# Zoom_Camrea_Controller_V3_0.net
KiCad netlist of a schematic drawn in Altium Designer
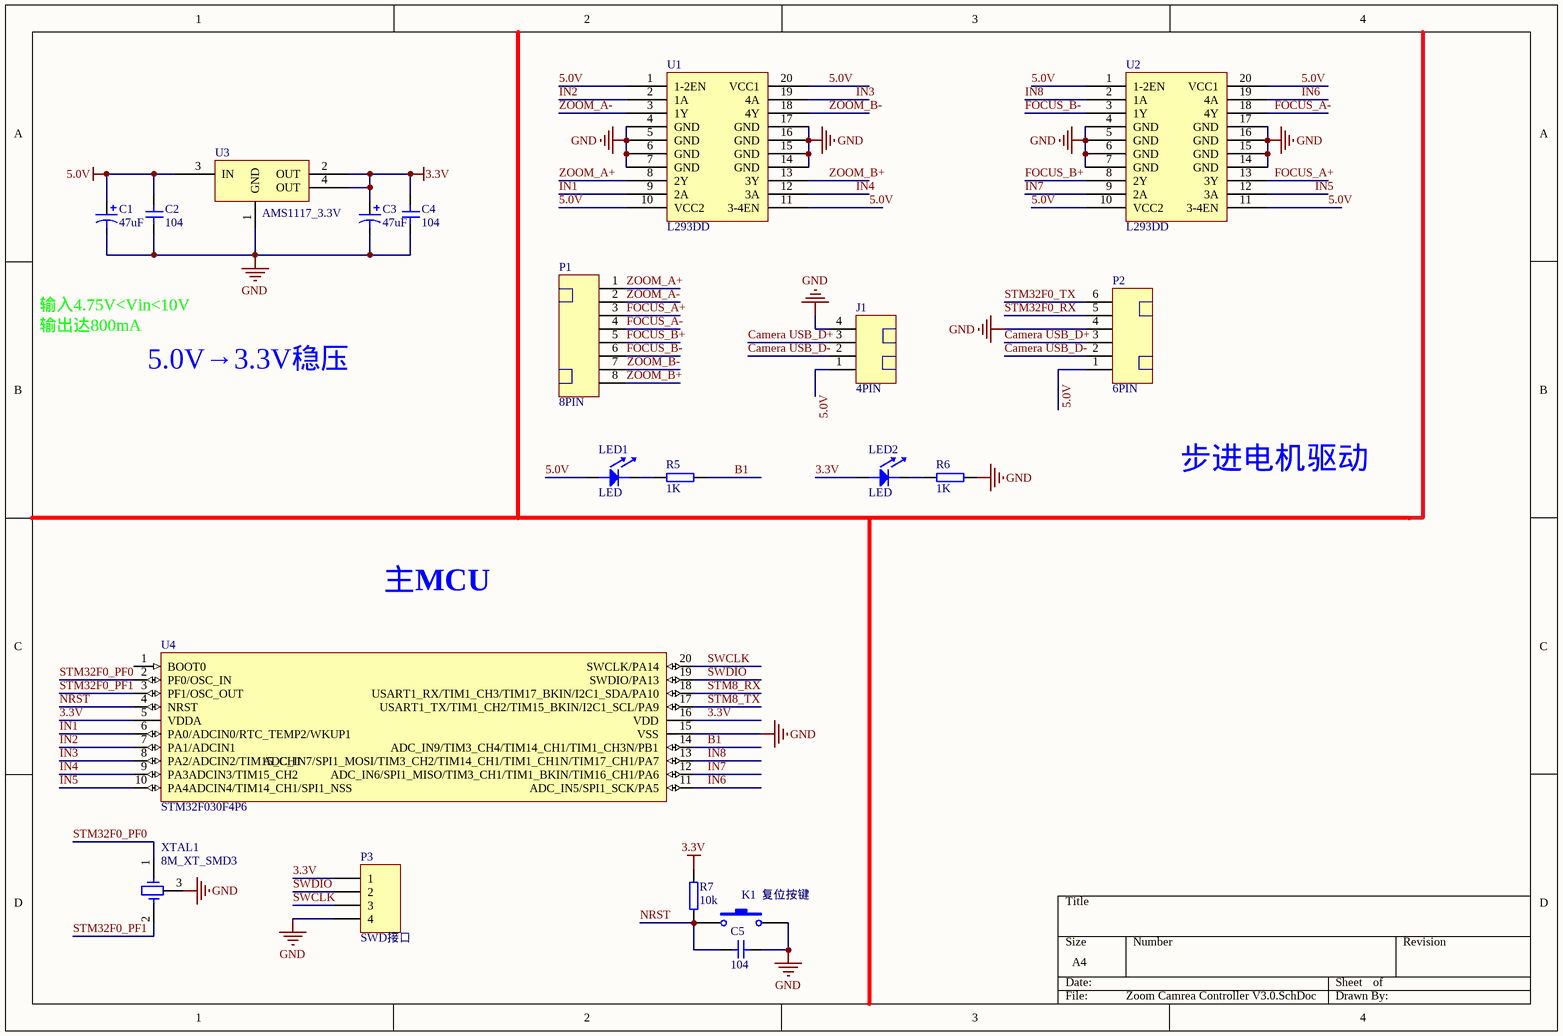
[diagram p0: Zoom Camrea Controller V3.0.SchDoc]

(export (version "E")
  (design (tool "Eeschema 10.0.6"))
  (components
    (comp (ref "C1")
      (value "47uF")
      (footprint "TAJ-A")
      (description "极性贴片电容")
      (libsource (lib "集大电协1.1.0") (part "Pol Cap"))
    )
    (comp (ref "C2")
      (value "104")
      (footprint "0805C")
      (description "无极贴片电容")
      (libsource (lib "集大电协1.1.0") (part "Cap1"))
    )
    (comp (ref "C3")
      (value "47uF")
      (footprint "TAJ-A")
      (description "极性贴片电容")
      (libsource (lib "集大电协1.1.0") (part "Pol Cap"))
    )
    (comp (ref "C4")
      (value "104")
      (footprint "0805C")
      (description "无极贴片电容")
      (libsource (lib "集大电协1.1.0") (part "Cap1"))
    )
    (comp (ref "C5")
      (value "104")
      (footprint "0805C")
      (description "无极贴片电容")
      (libsource (lib "集大电协1.1.0") (part "Cap1"))
    )
    (comp (ref "J1") (value "4PIN") (footprint "MX1.25WS-4P") (libsource (lib "MX") (part "MX1.25-4P")))
    (comp (ref "K1")
      (value "复位按键")
      (footprint "贴片按键")
      (description "轻触开关")
      (libsource (lib "集大电协1.1.0") (part "贴片按键"))
    )
    (comp (ref "LED1")
      (value "LED")
      (footprint "0805LED(RED)")
      (description "发光二极管")
      (libsource (lib "集大电协1.5") (part "LED"))
    )
    (comp (ref "LED2")
      (value "LED")
      (footprint "0805LED(RED)")
      (description "发光二极管")
      (libsource (lib "集大电协1.5") (part "LED"))
    )
    (comp (ref "P1") (value "8PIN") (footprint "MX1.25WS-8P") (libsource (lib "MX") (part "MX1.25-8P")))
    (comp (ref "P2") (value "6PIN") (footprint "MX1.25WS-6P") (libsource (lib "MX") (part "MX1.25-6P")))
    (comp (ref "P3")
      (value "SWD接口")
      (footprint "Header 4")
      (description "Header, 4-Pin")
      (fields (field (name "PUBLISHER") "Altium Limited"))
      (libsource (lib "Miscellaneous Connectors") (part "Header 4"))
    )
    (comp (ref "R5")
      (value "1K")
      (footprint "0805R")
      (description "电阻")
      (libsource (lib "集大电协1.1.2") (part "Res"))
    )
    (comp (ref "R6")
      (value "1K")
      (footprint "0805R")
      (description "电阻")
      (libsource (lib "集大电协1.1.2") (part "Res"))
    )
    (comp (ref "R7")
      (value "10k")
      (footprint "0805R")
      (description "电阻")
      (libsource (lib "集大电协1.1.0") (part "Res"))
    )
    (comp (ref "U1") (value "L293DD") (footprint "SOP-20") (libsource (lib "集大电协1.1.2") (part "L293D")))
    (comp (ref "U2") (value "L293DD") (footprint "SOP-20") (libsource (lib "集大电协1.1.2") (part "L293D")))
    (comp (ref "U3")
      (value "AMS1117_3.3V")
      (footprint "SOT-223")
      (description "电源芯片")
      (libsource (lib "集大电协1.1.0") (part "AMS1117-3.3V/5.0V"))
    )
    (comp (ref "U4")
      (value "STM32F030F4P6")
      (footprint "STM32F030")
      (libsource (lib "STM32系列单片机") (part "STM32F030F4P6"))
    )
    (comp (ref "XTAL1")
      (value "8M_XT_SMD3")
      (footprint "三脚贴片8M晶振")
      (libsource (lib "集大电协1.1.0") (part "XTAL三脚贴片晶振"))
    )
  )
  (nets
    (net (code "1") (name "/B1") (class "Default")
      (node (ref "R5") (pin "2") (pinfunction "2_2") (pintype "passive"))
      (node (ref "U4") (pin "14") (pinfunction "ADC_IN9/TIM3_CH4/TIM14_CH1/TIM1_CH3N/PB1_14") (pintype "bidirectional"))
    )
    (net (code "2") (name "/Camera USB_D+") (class "Default")
      (node (ref "J1") (pin "3") (pinfunction "3_3") (pintype "passive"))
      (node (ref "P2") (pin "3") (pinfunction "3_3") (pintype "passive"))
    )
    (net (code "3") (name "/Camera USB_D-") (class "Default")
      (node (ref "J1") (pin "2") (pinfunction "2_2") (pintype "passive"))
      (node (ref "P2") (pin "2") (pinfunction "2_2") (pintype "passive"))
    )
    (net (code "4") (name "/FOCUS_A+") (class "Default")
      (node (ref "P1") (pin "3") (pinfunction "3_3") (pintype "passive"))
      (node (ref "U2") (pin "13") (pinfunction "3Y_13") (pintype "passive"))
    )
    (net (code "5") (name "/FOCUS_A-") (class "Default")
      (node (ref "P1") (pin "4") (pinfunction "4_4") (pintype "passive"))
      (node (ref "U2") (pin "18") (pinfunction "4Y_18") (pintype "passive"))
    )
    (net (code "6") (name "/FOCUS_B+") (class "Default")
      (node (ref "P1") (pin "5") (pinfunction "5_5") (pintype "passive"))
      (node (ref "U2") (pin "8") (pinfunction "2Y_8") (pintype "passive"))
    )
    (net (code "7") (name "/FOCUS_B-") (class "Default")
      (node (ref "P1") (pin "6") (pinfunction "6_6") (pintype "passive"))
      (node (ref "U2") (pin "3") (pinfunction "1Y_3") (pintype "passive"))
    )
    (net (code "8") (name "/IN1") (class "Default")
      (node (ref "U1") (pin "9") (pinfunction "2A_9") (pintype "passive"))
      (node (ref "U4") (pin "6") (pinfunction "PA0/ADCIN0/RTC_TEMP2/WKUP1_6") (pintype "bidirectional"))
    )
    (net (code "9") (name "/IN2") (class "Default")
      (node (ref "U1") (pin "2") (pinfunction "1A_2") (pintype "passive"))
      (node (ref "U4") (pin "7") (pinfunction "PA1/ADCIN1_7") (pintype "bidirectional"))
    )
    (net (code "10") (name "/IN3") (class "Default")
      (node (ref "U1") (pin "19") (pinfunction "4A_19") (pintype "passive"))
      (node (ref "U4") (pin "8") (pinfunction "PA2/ADCIN2/TIM15_CH1_8") (pintype "bidirectional"))
    )
    (net (code "11") (name "/IN4") (class "Default")
      (node (ref "U1") (pin "12") (pinfunction "3A_12") (pintype "passive"))
      (node (ref "U4") (pin "9") (pinfunction "PA3ADCIN3/TIM15_CH2_9") (pintype "bidirectional"))
    )
    (net (code "12") (name "/IN5") (class "Default")
      (node (ref "U2") (pin "12") (pinfunction "3A_12") (pintype "passive"))
      (node (ref "U4") (pin "10") (pinfunction "PA4ADCIN4/TIM14_CH1/SPI1_NSS_10") (pintype "bidirectional"))
    )
    (net (code "13") (name "/IN6") (class "Default")
      (node (ref "U2") (pin "19") (pinfunction "4A_19") (pintype "passive"))
      (node (ref "U4") (pin "11") (pinfunction "ADC_IN5/SPI1_SCK/PA5_11") (pintype "bidirectional"))
    )
    (net (code "14") (name "/IN7") (class "Default")
      (node (ref "U2") (pin "9") (pinfunction "2A_9") (pintype "passive"))
      (node (ref "U4") (pin "12") (pinfunction "ADC_IN6/SPI1_MISO/TIM3_CH1/TIM1_BKIN/TIM16_CH1/PA6_12") (pintype "bidirectional"))
    )
    (net (code "15") (name "/IN8") (class "Default")
      (node (ref "U2") (pin "2") (pinfunction "1A_2") (pintype "passive"))
      (node (ref "U4") (pin "13") (pinfunction "ADC_IN7/SPI1_MOSI/TIM3_CH2/TIM14_CH1/TIM1_CH1N/TIM17_CH1/PA7_13") (pintype "bidirectional"))
    )
    (net (code "16") (name "/NRST") (class "Default")
      (node (ref "C5") (pin "2") (pinfunction "2_2") (pintype "passive"))
      (node (ref "K1") (pin "1") (pinfunction "1_1") (pintype "passive"))
      (node (ref "R7") (pin "1") (pinfunction "1_1") (pintype "passive"))
      (node (ref "U4") (pin "4") (pinfunction "NRST_4") (pintype "bidirectional"))
    )
    (net (code "17") (name "/STM8_RX") (class "Default")
      (node (ref "U4") (pin "18") (pinfunction "USART1_RX/TIM1_CH3/TIM17_BKIN/I2C1_SDA/PA10_18") (pintype "bidirectional"))
    )
    (net (code "18") (name "/STM8_TX") (class "Default")
      (node (ref "U4") (pin "17") (pinfunction "USART1_TX/TIM1_CH2/TIM15_BKIN/I2C1_SCL/PA9_17") (pintype "bidirectional"))
    )
    (net (code "19") (name "/STM32F0_PF0") (class "Default")
      (node (ref "U4") (pin "2") (pinfunction "PF0/OSC_IN_2") (pintype "bidirectional"))
      (node (ref "XTAL1") (pin "1") (pinfunction "1_1") (pintype "passive"))
    )
    (net (code "20") (name "/STM32F0_PF1") (class "Default")
      (node (ref "U4") (pin "3") (pinfunction "PF1/OSC_OUT_3") (pintype "bidirectional"))
      (node (ref "XTAL1") (pin "2") (pinfunction "2_2") (pintype "passive"))
    )
    (net (code "21") (name "/STM32F0_RX") (class "Default")
      (node (ref "P2") (pin "5") (pinfunction "5_5") (pintype "passive"))
    )
    (net (code "22") (name "/STM32F0_TX") (class "Default")
      (node (ref "P2") (pin "6") (pinfunction "6_6") (pintype "passive"))
    )
    (net (code "23") (name "/SWCLK") (class "Default")
      (node (ref "P3") (pin "3") (pinfunction "3_3") (pintype "passive"))
      (node (ref "U4") (pin "20") (pinfunction "SWCLK/PA14_20") (pintype "bidirectional"))
    )
    (net (code "24") (name "/SWDIO") (class "Default")
      (node (ref "P3") (pin "2") (pinfunction "2_2") (pintype "passive"))
      (node (ref "U4") (pin "19") (pinfunction "SWDIO/PA13_19") (pintype "bidirectional"))
    )
    (net (code "25") (name "/ZOOM_A+") (class "Default")
      (node (ref "P1") (pin "1") (pinfunction "1_1") (pintype "passive"))
      (node (ref "U1") (pin "8") (pinfunction "2Y_8") (pintype "passive"))
    )
    (net (code "26") (name "/ZOOM_A-") (class "Default")
      (node (ref "P1") (pin "2") (pinfunction "2_2") (pintype "passive"))
      (node (ref "U1") (pin "3") (pinfunction "1Y_3") (pintype "passive"))
    )
    (net (code "27") (name "/ZOOM_B+") (class "Default")
      (node (ref "P1") (pin "8") (pinfunction "8_8") (pintype "passive"))
      (node (ref "U1") (pin "13") (pinfunction "3Y_13") (pintype "passive"))
    )
    (net (code "28") (name "/ZOOM_B-") (class "Default")
      (node (ref "P1") (pin "7") (pinfunction "7_7") (pintype "passive"))
      (node (ref "U1") (pin "18") (pinfunction "4Y_18") (pintype "passive"))
    )
    (net (code "29") (name "3.3V") (class "Default")
      (node (ref "C3") (pin "1") (pinfunction "1_1") (pintype "passive"))
      (node (ref "C4") (pin "2") (pinfunction "2_2") (pintype "passive"))
      (node (ref "LED2") (pin "1") (pintype "passive"))
      (node (ref "P3") (pin "1") (pinfunction "1_1") (pintype "passive"))
      (node (ref "R7") (pin "2") (pinfunction "2_2") (pintype "passive"))
      (node (ref "U3") (pin "2") (pinfunction "OUT_2") (pintype "passive"))
      (node (ref "U3") (pin "4") (pinfunction "OUT_4") (pintype "passive"))
      (node (ref "U4") (pin "16") (pinfunction "VDD_16") (pintype "power_in"))
      (node (ref "U4") (pin "5") (pinfunction "VDDA_5") (pintype "power_in"))
    )
    (net (code "30") (name "5.0V") (class "Default")
      (node (ref "C1") (pin "1") (pinfunction "1_1") (pintype "passive"))
      (node (ref "C2") (pin "2") (pinfunction "2_2") (pintype "passive"))
      (node (ref "J1") (pin "1") (pinfunction "1_1") (pintype "passive"))
      (node (ref "LED1") (pin "1") (pintype "passive"))
      (node (ref "P2") (pin "1") (pinfunction "1_1") (pintype "passive"))
      (node (ref "U1") (pin "1") (pinfunction "1-2EN_1") (pintype "passive"))
      (node (ref "U1") (pin "10") (pinfunction "VCC2_10") (pintype "passive"))
      (node (ref "U1") (pin "11") (pinfunction "3-4EN_11") (pintype "passive"))
      (node (ref "U1") (pin "20") (pinfunction "VCC1_20") (pintype "passive"))
      (node (ref "U2") (pin "1") (pinfunction "1-2EN_1") (pintype "passive"))
      (node (ref "U2") (pin "10") (pinfunction "VCC2_10") (pintype "passive"))
      (node (ref "U2") (pin "11") (pinfunction "3-4EN_11") (pintype "passive"))
      (node (ref "U2") (pin "20") (pinfunction "VCC1_20") (pintype "passive"))
      (node (ref "U3") (pin "3") (pinfunction "IN_3") (pintype "passive"))
    )
    (net (code "31") (name "GND") (class "Default")
      (node (ref "C1") (pin "2") (pinfunction "2_2") (pintype "passive"))
      (node (ref "C2") (pin "1") (pinfunction "1_1") (pintype "passive"))
      (node (ref "C3") (pin "2") (pinfunction "2_2") (pintype "passive"))
      (node (ref "C4") (pin "1") (pinfunction "1_1") (pintype "passive"))
      (node (ref "C5") (pin "1") (pinfunction "1_1") (pintype "passive"))
      (node (ref "J1") (pin "4") (pinfunction "4_4") (pintype "passive"))
      (node (ref "K1") (pin "2") (pinfunction "2_2") (pintype "passive"))
      (node (ref "P2") (pin "4") (pinfunction "4_4") (pintype "passive"))
      (node (ref "P3") (pin "4") (pinfunction "4_4") (pintype "passive"))
      (node (ref "R6") (pin "2") (pinfunction "2_2") (pintype "passive"))
      (node (ref "U1") (pin "14") (pinfunction "GND_14") (pintype "passive"))
      (node (ref "U1") (pin "15") (pinfunction "GND_15") (pintype "passive"))
      (node (ref "U1") (pin "16") (pinfunction "GND_16") (pintype "passive"))
      (node (ref "U1") (pin "17") (pinfunction "GND_17") (pintype "passive"))
      (node (ref "U1") (pin "4") (pinfunction "GND_4") (pintype "passive"))
      (node (ref "U1") (pin "5") (pinfunction "GND_5") (pintype "passive"))
      (node (ref "U1") (pin "6") (pinfunction "GND_6") (pintype "passive"))
      (node (ref "U1") (pin "7") (pinfunction "GND_7") (pintype "passive"))
      (node (ref "U2") (pin "14") (pinfunction "GND_14") (pintype "passive"))
      (node (ref "U2") (pin "15") (pinfunction "GND_15") (pintype "passive"))
      (node (ref "U2") (pin "16") (pinfunction "GND_16") (pintype "passive"))
      (node (ref "U2") (pin "17") (pinfunction "GND_17") (pintype "passive"))
      (node (ref "U2") (pin "4") (pinfunction "GND_4") (pintype "passive"))
      (node (ref "U2") (pin "5") (pinfunction "GND_5") (pintype "passive"))
      (node (ref "U2") (pin "6") (pinfunction "GND_6") (pintype "passive"))
      (node (ref "U2") (pin "7") (pinfunction "GND_7") (pintype "passive"))
      (node (ref "U3") (pin "1") (pinfunction "GND_1") (pintype "passive"))
      (node (ref "U4") (pin "15") (pinfunction "VSS_15") (pintype "power_in"))
      (node (ref "XTAL1") (pin "3") (pinfunction "3_3") (pintype "passive"))
    )
    (net (code "32") (name "Net-(LED1-Pad2)") (class "Default")
      (node (ref "LED1") (pin "2") (pinfunction "2_2") (pintype "passive"))
      (node (ref "R5") (pin "1") (pinfunction "1_1") (pintype "passive"))
    )
    (net (code "33") (name "Net-(LED2-Pad2)") (class "Default")
      (node (ref "LED2") (pin "2") (pinfunction "2_2") (pintype "passive"))
      (node (ref "R6") (pin "1") (pinfunction "1_1") (pintype "passive"))
    )
    (net (code "34") (name "unconnected-(U4-BOOT0-Pad1)") (class "Default")
      (node (ref "U4") (pin "1") (pinfunction "BOOT0_1") (pintype "input"))
    )
  )
)
